# POS.net
KiCad netlist of a schematic drawn in Altium Designer
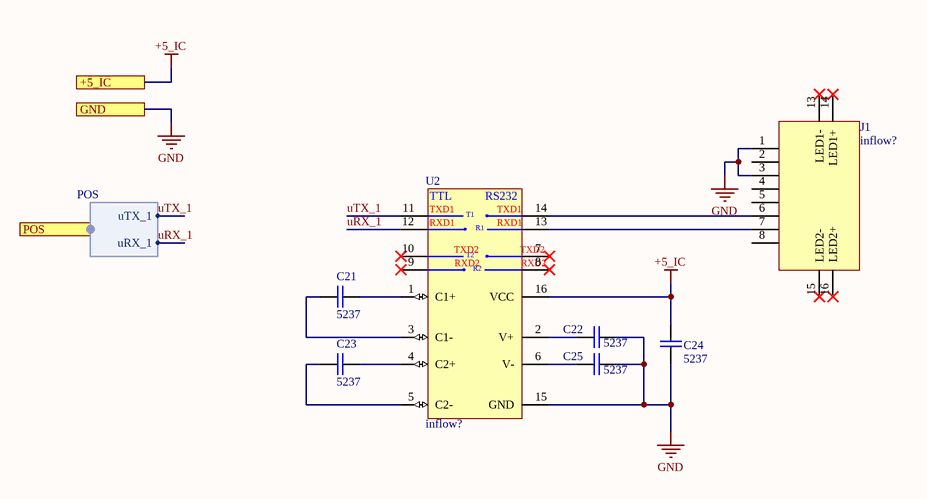
[diagram p0: POS.SchDoc]

(export (version "E")
  (design (tool "Eeschema 10.0.6"))
  (components
    (comp (ref "C21")
      (value "1u'F, 50'V")
      (footprint "CAP 1206/3216")
      (description "Bipolar ceramic capacitor SMD")
      (fields (field (name "INFLOW") "5237") (field (name "VALIDATION") "Valid"))
      (libsource (lib "aKaReZa") (part "Cap_Multi_1u_50_1206"))
    )
    (comp (ref "C22")
      (value "1u'F, 50'V")
      (footprint "CAP 1206/3216")
      (description "Bipolar ceramic capacitor SMD")
      (fields (field (name "INFLOW") "5237") (field (name "VALIDATION") "Valid"))
      (libsource (lib "aKaReZa") (part "Cap_Multi_1u_50_1206"))
    )
    (comp (ref "C23")
      (value "1u'F, 50'V")
      (footprint "CAP 1206/3216")
      (description "Bipolar ceramic capacitor SMD")
      (fields (field (name "INFLOW") "5237") (field (name "VALIDATION") "Valid"))
      (libsource (lib "aKaReZa") (part "Cap_Multi_1u_50_1206"))
    )
    (comp (ref "C24")
      (value "1u'F, 50'V")
      (footprint "CAP 1206/3216")
      (description "Bipolar ceramic capacitor SMD")
      (fields (field (name "INFLOW") "5237") (field (name "VALIDATION") "Valid"))
      (libsource (lib "aKaReZa") (part "Cap_Multi_1u_50_1206"))
    )
    (comp (ref "C25")
      (value "1u'F, 50'V")
      (footprint "CAP 1206/3216")
      (description "Bipolar ceramic capacitor SMD")
      (fields (field (name "INFLOW") "5237") (field (name "VALIDATION") "Valid"))
      (libsource (lib "aKaReZa") (part "Cap_Multi_1u_50_1206"))
    )
    (comp (ref "J1")
      (value "RJ45, mini")
      (footprint "RJ45_MINI")
      (description "RJ45 Mini With two LEDs")
      (fields (field (name "INFLOW") "inflow?") (field (name "VALIDATION") "NT"))
      (libsource (lib "aKaReZa") (part "Con_PC_RJ45_MINI"))
    )
    (comp (ref "U2")
      (value "MAX3232")
      (footprint "NSO16_M")
      (fields (field (name "INFLOW") "inflow?") (field (name "VALIDATION") "Valid"))
      (libsource (lib "vending-pad-002") (part "IC_Converter_MAX3232CSE"))
    )
  )
  (nets
    (net (code "2") (name "+5_IC") (class "Default")
      (node (ref "C24") (pin "1") (pinfunction "1_1") (pintype "passive"))
      (node (ref "U2") (pin "16") (pinfunction "VCC_16") (pintype "power_in"))
    )
    (net (code "3") (name "/uRX_1") (class "Default")
      (node (ref "U2") (pin "12") (pinfunction "R1OUT_12") (pintype "passive"))
    )
    (net (code "4") (name "/uTX_1") (class "Default")
      (node (ref "U2") (pin "11") (pinfunction "T1IN_11") (pintype "passive"))
    )
    (net (code "6") (name "GND") (class "Default")
      (node (ref "C22") (pin "2") (pinfunction "2_2") (pintype "passive"))
      (node (ref "C24") (pin "2") (pinfunction "2_2") (pintype "passive"))
      (node (ref "C25") (pin "2") (pinfunction "2_2") (pintype "passive"))
      (node (ref "J1") (pin "1") (pintype "passive"))
      (node (ref "J1") (pin "3") (pintype "passive"))
      (node (ref "U2") (pin "15") (pinfunction "GND_15") (pintype "power_in"))
    )
    (net (code "7") (name "Net-(U2-C1+)") (class "Default")
      (node (ref "C21") (pin "1") (pinfunction "1_1") (pintype "passive"))
      (node (ref "U2") (pin "1") (pinfunction "C1+_1") (pintype "bidirectional"))
    )
    (net (code "8") (name "Net-(U2-C1-)") (class "Default")
      (node (ref "C21") (pin "2") (pinfunction "2_2") (pintype "passive"))
      (node (ref "U2") (pin "3") (pinfunction "C1-_3") (pintype "bidirectional"))
    )
    (net (code "9") (name "Net-(U2-C2+)") (class "Default")
      (node (ref "C23") (pin "1") (pinfunction "1_1") (pintype "passive"))
      (node (ref "U2") (pin "4") (pinfunction "C2+_4") (pintype "bidirectional"))
    )
    (net (code "10") (name "Net-(U2-C2-)") (class "Default")
      (node (ref "C23") (pin "2") (pinfunction "2_2") (pintype "passive"))
      (node (ref "U2") (pin "5") (pinfunction "C2-_5") (pintype "bidirectional"))
    )
    (net (code "11") (name "Net-(U2-R1IN)") (class "Default")
      (node (ref "J1") (pin "7") (pintype "passive"))
      (node (ref "U2") (pin "13") (pinfunction "R1IN_13") (pintype "passive"))
    )
    (net (code "12") (name "Net-(U2-T1OUT)") (class "Default")
      (node (ref "J1") (pin "6") (pintype "passive"))
      (node (ref "U2") (pin "14") (pinfunction "T1OUT_14") (pintype "passive"))
    )
    (net (code "13") (name "Net-(U2-V+)") (class "Default")
      (node (ref "C22") (pin "1") (pinfunction "1_1") (pintype "passive"))
      (node (ref "U2") (pin "2") (pinfunction "V+_2") (pintype "power_in"))
    )
    (net (code "14") (name "Net-(U2-V-)") (class "Default")
      (node (ref "C25") (pin "1") (pinfunction "1_1") (pintype "passive"))
      (node (ref "U2") (pin "6") (pinfunction "V-_6") (pintype "power_in"))
    )
    (net (code "15") (name "unconnected-(J1-LED1+-Pad14)") (class "Default")
      (node (ref "J1") (pin "14") (pinfunction "LED1+_14") (pintype "passive+no_connect"))
    )
    (net (code "16") (name "unconnected-(J1-LED1--Pad13)") (class "Default")
      (node (ref "J1") (pin "13") (pinfunction "LED1-_13") (pintype "passive+no_connect"))
    )
    (net (code "17") (name "unconnected-(J1-LED2+-Pad16)") (class "Default")
      (node (ref "J1") (pin "16") (pinfunction "LED2+_16") (pintype "passive+no_connect"))
    )
    (net (code "18") (name "unconnected-(J1-LED2--Pad15)") (class "Default")
      (node (ref "J1") (pin "15") (pinfunction "LED2-_15") (pintype "passive+no_connect"))
    )
    (net (code "19") (name "unconnected-(J1-Pad2)") (class "Default")
      (node (ref "J1") (pin "2") (pintype "passive"))
    )
    (net (code "20") (name "unconnected-(J1-Pad4)") (class "Default")
      (node (ref "J1") (pin "4") (pintype "passive"))
    )
    (net (code "21") (name "unconnected-(J1-Pad5)") (class "Default")
      (node (ref "J1") (pin "5") (pintype "passive"))
    )
    (net (code "22") (name "unconnected-(J1-Pad8)") (class "Default")
      (node (ref "J1") (pin "8") (pintype "passive"))
    )
    (net (code "23") (name "unconnected-(U2-R2IN-Pad8)") (class "Default")
      (node (ref "U2") (pin "8") (pinfunction "R2IN_8") (pintype "passive+no_connect"))
    )
    (net (code "24") (name "unconnected-(U2-R2OUT-Pad9)") (class "Default")
      (node (ref "U2") (pin "9") (pinfunction "R2OUT_9") (pintype "passive+no_connect"))
    )
    (net (code "25") (name "unconnected-(U2-T2IN-Pad10)") (class "Default")
      (node (ref "U2") (pin "10") (pinfunction "T2IN_10") (pintype "passive+no_connect"))
    )
    (net (code "26") (name "unconnected-(U2-T2OUT-Pad7)") (class "Default")
      (node (ref "U2") (pin "7") (pinfunction "T2OUT_7") (pintype "passive+no_connect"))
    )
  )
)
